# boardSchematic.net
KiCad netlist of a schematic drawn in EAGLE
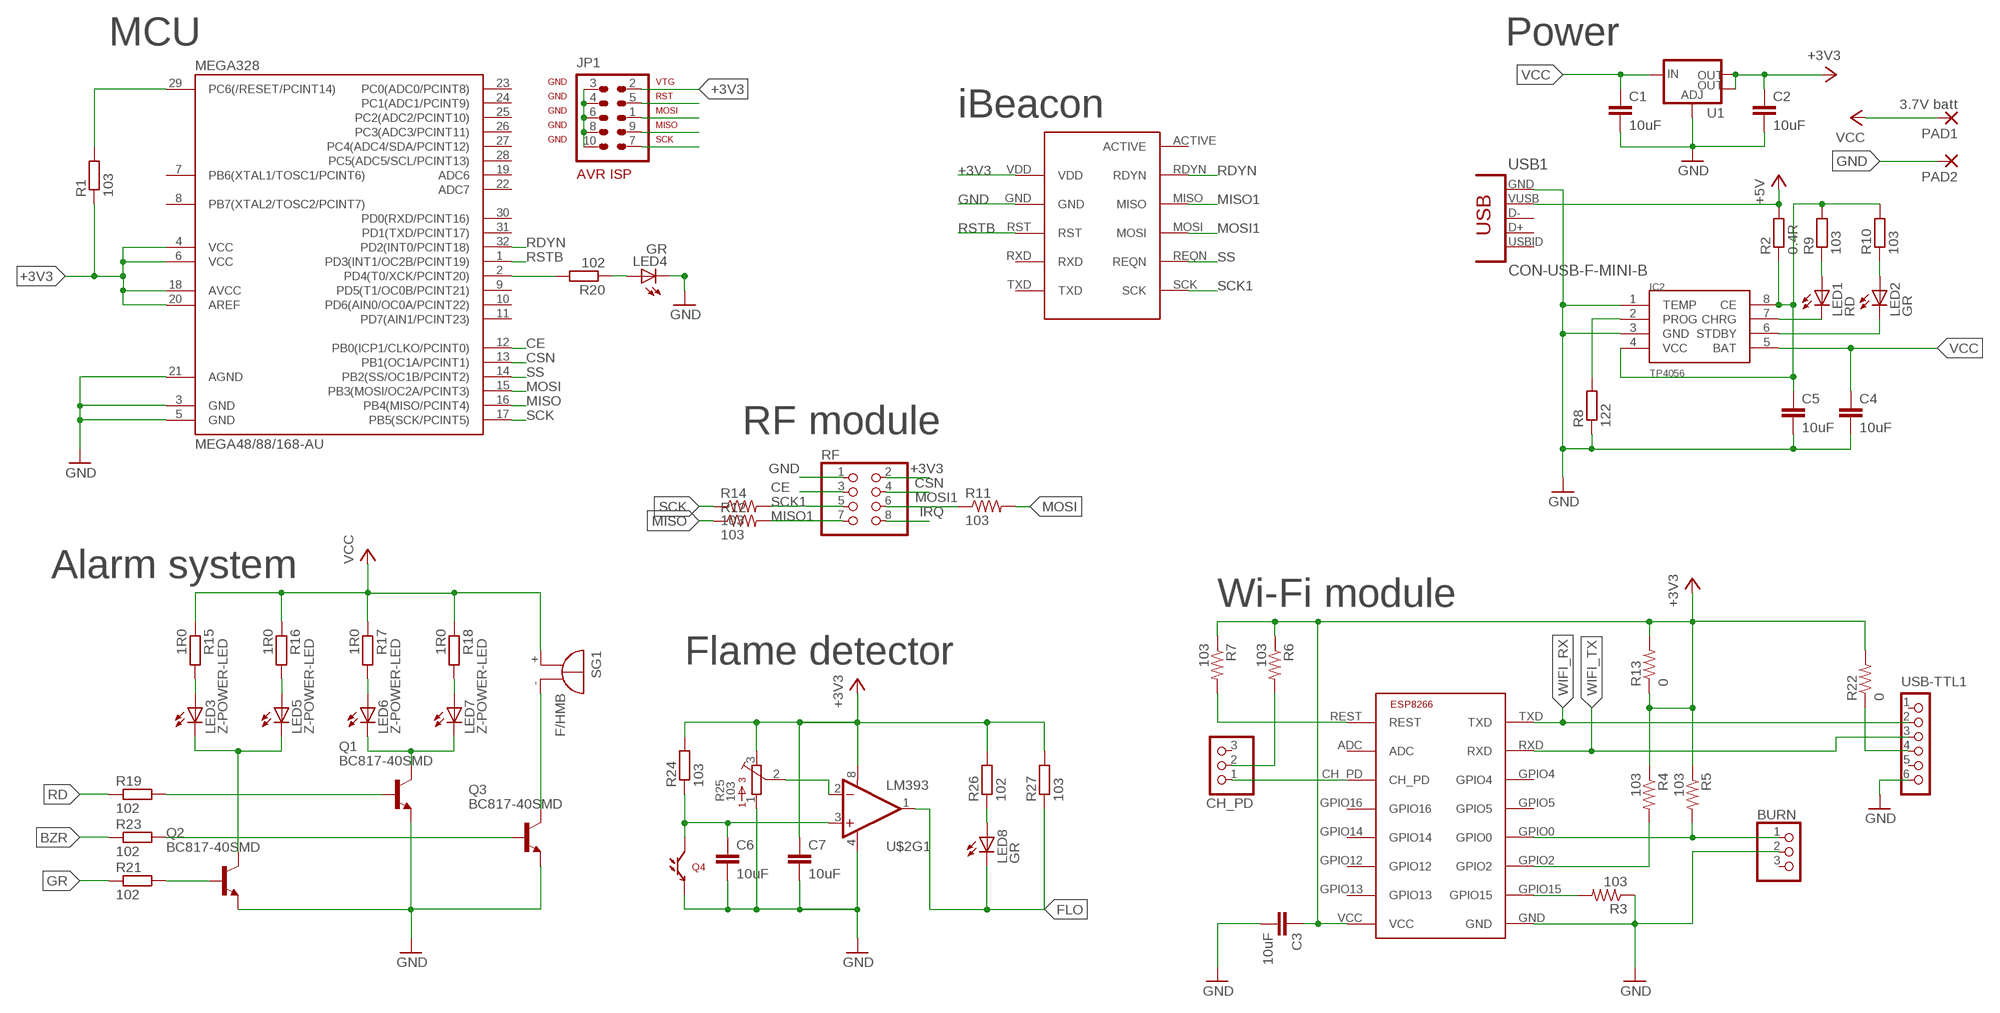
[diagram p0: schematic, sheet 1]

(export (version "E")
  (design (tool "Eeschema 10.0.6"))
  (components
    (comp (ref "BEACON")
      (value "MOD-NRF8001MOD-NRF8001")
      (footprint "eagle-import:MOD-NRF8001")
      (libsource (lib "eagle-import") (part "MOD-NRF8001MOD-NRF8001"))
    )
    (comp (ref "BURN")
      (value "PINHD-1X3")
      (footprint "eagle-import:1X03")
      (libsource (lib "eagle-import") (part "PINHD-1X3"))
    )
    (comp (ref "C1")
      (value "10uF")
      (footprint "eagle-import:C0805")
      (libsource (lib "eagle-import") (part "C-EUC0805"))
    )
    (comp (ref "C2")
      (value "10uF")
      (footprint "eagle-import:C0805")
      (libsource (lib "eagle-import") (part "C-EUC0805"))
    )
    (comp (ref "C3")
      (value "10uF")
      (footprint "eagle-import:C0805")
      (libsource (lib "eagle-import") (part "C-EUC0805"))
    )
    (comp (ref "C4")
      (value "10uF")
      (footprint "eagle-import:C1210")
      (libsource (lib "eagle-import") (part "C-EUC1210"))
    )
    (comp (ref "C5")
      (value "10uF")
      (footprint "eagle-import:C1210")
      (libsource (lib "eagle-import") (part "C-EUC1210"))
    )
    (comp (ref "C6")
      (value "10uF")
      (footprint "eagle-import:C0805")
      (libsource (lib "eagle-import") (part "C-EUC0805"))
    )
    (comp (ref "C7")
      (value "10uF")
      (footprint "eagle-import:C0805")
      (libsource (lib "eagle-import") (part "C-EUC0805"))
    )
    (comp (ref "CH_PD")
      (value "PINHD-1X3")
      (footprint "eagle-import:1X03")
      (libsource (lib "eagle-import") (part "PINHD-1X3"))
    )
    (comp (ref "IC2")
      (value "TP4056")
      (footprint "eagle-import:SOP-8")
      (libsource (lib "eagle-import") (part "TP4056"))
    )
    (comp (ref "JP1")
      (value "AVR-ISP-10")
      (footprint "eagle-import:AVR-ISP-10")
      (libsource (lib "eagle-import") (part "AVR-ISP-10"))
    )
    (comp (ref "LED1")
      (value "RD")
      (footprint "eagle-import:SML0805")
      (libsource (lib "eagle-import") (part "LEDSML0805"))
    )
    (comp (ref "LED2")
      (value "GR")
      (footprint "eagle-import:SML0805")
      (libsource (lib "eagle-import") (part "LEDSML0805"))
    )
    (comp (ref "LED3")
      (value "Z-POWER-LED")
      (footprint "eagle-import:Z-POWER-LED-PCB-TYPE")
      (libsource (lib "eagle-import") (part "Z-POWER-LED"))
    )
    (comp (ref "LED4")
      (value "GR")
      (footprint "eagle-import:SML0805")
      (libsource (lib "eagle-import") (part "LEDSML0805"))
    )
    (comp (ref "LED5")
      (value "Z-POWER-LED")
      (footprint "eagle-import:Z-POWER-LED-PCB-TYPE")
      (libsource (lib "eagle-import") (part "Z-POWER-LED"))
    )
    (comp (ref "LED6")
      (value "Z-POWER-LED")
      (footprint "eagle-import:Z-POWER-LED-PCB-TYPE")
      (libsource (lib "eagle-import") (part "Z-POWER-LED"))
    )
    (comp (ref "LED7")
      (value "Z-POWER-LED")
      (footprint "eagle-import:Z-POWER-LED-PCB-TYPE")
      (libsource (lib "eagle-import") (part "Z-POWER-LED"))
    )
    (comp (ref "LED8")
      (value "GR")
      (footprint "eagle-import:SML0805")
      (libsource (lib "eagle-import") (part "LEDSML0805"))
    )
    (comp (ref "MEGA328")
      (value "MEGA48/88/168-AU")
      (footprint "eagle-import:TQFP32-08")
      (libsource (lib "eagle-import") (part "MEGA48/88/168-AU"))
    )
    (comp (ref "PAD1")
      (value "3.7V batt")
      (footprint "eagle-import:SMD2,54-5,08")
      (libsource (lib "eagle-import") (part "SMD5"))
    )
    (comp (ref "PAD2")
      (value "SMD5")
      (footprint "eagle-import:SMD2,54-5,08")
      (libsource (lib "eagle-import") (part "SMD5"))
    )
    (comp (ref "Q1")
      (value "BC817-40SMD")
      (footprint "eagle-import:SOT23-BEC")
      (libsource (lib "eagle-import") (part "BC817SMD-40"))
    )
    (comp (ref "Q2")
      (value "BC817-40SMD")
      (footprint "eagle-import:SOT23-BEC")
      (libsource (lib "eagle-import") (part "BC817SMD-40"))
    )
    (comp (ref "Q3")
      (value "BC817-40SMD")
      (footprint "eagle-import:SOT23-BEC")
      (libsource (lib "eagle-import") (part "BC817SMD-40"))
    )
    (comp (ref "Q4")
      (value "LTR-301")
      (footprint "eagle-import:LTR-301")
      (libsource (lib "eagle-import") (part "LTR-301"))
    )
    (comp (ref "R1")
      (value "103")
      (footprint "eagle-import:R0805")
      (libsource (lib "eagle-import") (part "R-EU_R0805"))
    )
    (comp (ref "R2")
      (value "0.4R")
      (footprint "eagle-import:R1210W")
      (libsource (lib "eagle-import") (part "R-EU_R1210W"))
    )
    (comp (ref "R3")
      (value "103")
      (footprint "eagle-import:R0805")
      (libsource (lib "eagle-import") (part "R-US_R0805"))
    )
    (comp (ref "R4")
      (value "103")
      (footprint "eagle-import:R0805")
      (libsource (lib "eagle-import") (part "R-US_R0805"))
    )
    (comp (ref "R5")
      (value "103")
      (footprint "eagle-import:R0805")
      (libsource (lib "eagle-import") (part "R-US_R0805"))
    )
    (comp (ref "R6")
      (value "103")
      (footprint "eagle-import:R0805")
      (libsource (lib "eagle-import") (part "R-US_R0805"))
    )
    (comp (ref "R7")
      (value "103")
      (footprint "eagle-import:R0805")
      (libsource (lib "eagle-import") (part "R-US_R0805"))
    )
    (comp (ref "R8")
      (value "122")
      (footprint "eagle-import:R0805")
      (libsource (lib "eagle-import") (part "R-EU_R0805"))
    )
    (comp (ref "R9")
      (value "103")
      (footprint "eagle-import:R0805")
      (libsource (lib "eagle-import") (part "R-EU_R0805"))
    )
    (comp (ref "R10")
      (value "103")
      (footprint "eagle-import:R0805")
      (libsource (lib "eagle-import") (part "R-EU_R0805"))
    )
    (comp (ref "R11")
      (value "103")
      (footprint "eagle-import:R0805")
      (libsource (lib "eagle-import") (part "R-US_R0805"))
    )
    (comp (ref "R12")
      (value "103")
      (footprint "eagle-import:R0805")
      (libsource (lib "eagle-import") (part "R-US_R0805"))
    )
    (comp (ref "R13")
      (value "0")
      (footprint "eagle-import:R1206")
      (libsource (lib "eagle-import") (part "R-US_R1206"))
    )
    (comp (ref "R14")
      (value "103")
      (footprint "eagle-import:R0805")
      (libsource (lib "eagle-import") (part "R-US_R0805"))
    )
    (comp (ref "R15")
      (value "1R0")
      (footprint "eagle-import:R1206")
      (libsource (lib "eagle-import") (part "R-EU_R1206"))
    )
    (comp (ref "R16")
      (value "1R0")
      (footprint "eagle-import:R1206")
      (libsource (lib "eagle-import") (part "R-EU_R1206"))
    )
    (comp (ref "R17")
      (value "1R0")
      (footprint "eagle-import:R1206")
      (libsource (lib "eagle-import") (part "R-EU_R1206"))
    )
    (comp (ref "R18")
      (value "1R0")
      (footprint "eagle-import:R1206")
      (libsource (lib "eagle-import") (part "R-EU_R1206"))
    )
    (comp (ref "R19")
      (value "102")
      (footprint "eagle-import:R0805")
      (libsource (lib "eagle-import") (part "R-EU_R0805"))
    )
    (comp (ref "R20")
      (value "102")
      (footprint "eagle-import:R0805")
      (libsource (lib "eagle-import") (part "R-EU_R0805"))
    )
    (comp (ref "R21")
      (value "102")
      (footprint "eagle-import:R0805")
      (libsource (lib "eagle-import") (part "R-EU_R0805"))
    )
    (comp (ref "R22")
      (value "0")
      (footprint "eagle-import:R1206")
      (libsource (lib "eagle-import") (part "R-US_R1206"))
    )
    (comp (ref "R23")
      (value "102")
      (footprint "eagle-import:R0805")
      (libsource (lib "eagle-import") (part "R-EU_R0805"))
    )
    (comp (ref "R24")
      (value "103")
      (footprint "eagle-import:R0805")
      (libsource (lib "eagle-import") (part "R-EU_R0805"))
    )
    (comp (ref "R25")
      (value "103")
      (footprint "eagle-import:3362P")
      (libsource (lib "eagle-import") (part "3362P"))
    )
    (comp (ref "R26")
      (value "102")
      (footprint "eagle-import:R0805")
      (libsource (lib "eagle-import") (part "R-EU_R0805"))
    )
    (comp (ref "R27")
      (value "103")
      (footprint "eagle-import:R0805")
      (libsource (lib "eagle-import") (part "R-EU_R0805"))
    )
    (comp (ref "RF")
      (value "PINHD-2X4")
      (footprint "eagle-import:2X04")
      (libsource (lib "eagle-import") (part "PINHD-2X4"))
    )
    (comp (ref "SG1")
      (value "F/HMB")
      (footprint "eagle-import:F_HMB")
      (libsource (lib "eagle-import") (part "F/HMB"))
    )
    (comp (ref "U$1")
      (value "ESP8266")
      (footprint "eagle-import:ESP-03")
      (libsource (lib "eagle-import") (part "ESP8266"))
    )
    (comp (ref "U$2")
      (value "LM393")
      (footprint "eagle-import:SO08")
      (libsource (lib "eagle-import") (part "LM393"))
    )
    (comp (ref "U1")
      (value "V_REG_LM1117SOT223")
      (footprint "eagle-import:SOT223")
      (libsource (lib "eagle-import") (part "V_REG_LM1117SOT223"))
    )
    (comp (ref "USB-TTL1")
      (value "CON_HEADER_1X06-SMD-RIGHT-ANGLED")
      (footprint "eagle-import:M1X6_MALE_RIGHT_ANGLED_SMD")
      (libsource (lib "eagle-import") (part "CON_HEADER_1X06-SMD-RIGHT-ANGLED"))
    )
    (comp (ref "USB1")
      (value "CON-USB-F-MINI-B")
      (footprint "eagle-import:CONN_USB_MINI-B")
      (libsource (lib "eagle-import") (part "CON-USB-F-MINI-B"))
    )
  )
  (nets
    (net (code "1") (name "+3V3") (class "Default")
      (node (ref "BEACON") (pin "VDD") (pinfunction "VDD_VDD") (pintype "power_in"))
      (node (ref "C2") (pin "1") (pinfunction "1_1") (pintype "passive"))
      (node (ref "C3") (pin "1") (pinfunction "1_1") (pintype "passive"))
      (node (ref "C7") (pin "1") (pinfunction "1_1") (pintype "passive"))
      (node (ref "JP1") (pin "2") (pinfunction "2_2") (pintype "passive"))
      (node (ref "MEGA328") (pin "18") (pinfunction "AVCC_18") (pintype "passive"))
      (node (ref "MEGA328") (pin "20") (pinfunction "AREF_20") (pintype "passive"))
      (node (ref "MEGA328") (pin "4") (pinfunction "VCC_4") (pintype "power_in"))
      (node (ref "MEGA328") (pin "6") (pinfunction "VCC_6") (pintype "power_in"))
      (node (ref "R1") (pin "1") (pinfunction "1_1") (pintype "passive"))
      (node (ref "R13") (pin "1") (pinfunction "1_1") (pintype "passive"))
      (node (ref "R13") (pin "2") (pinfunction "2_2") (pintype "passive"))
      (node (ref "R22") (pin "2") (pinfunction "2_2") (pintype "passive"))
      (node (ref "R24") (pin "2") (pinfunction "2_2") (pintype "passive"))
      (node (ref "R25") (pin "3") (pinfunction "3_3") (pintype "passive"))
      (node (ref "R26") (pin "2") (pinfunction "2_2") (pintype "passive"))
      (node (ref "R27") (pin "2") (pinfunction "2_2") (pintype "passive"))
      (node (ref "R4") (pin "1") (pinfunction "1_1") (pintype "passive"))
      (node (ref "R5") (pin "1") (pinfunction "1_1") (pintype "passive"))
      (node (ref "R6") (pin "1") (pinfunction "1_1") (pintype "passive"))
      (node (ref "R7") (pin "1") (pinfunction "1_1") (pintype "passive"))
      (node (ref "RF") (pin "2") (pinfunction "2_2") (pintype "passive"))
      (node (ref "U$1") (pin "VCC") (pinfunction "VCC_VCC") (pintype "bidirectional"))
      (node (ref "U$2") (pin "8") (pinfunction "V+_8") (pintype "power_in"))
      (node (ref "U1") (pin "2") (pinfunction "OUT_2") (pintype "output"))
      (node (ref "U1") (pin "4") (pinfunction "OUT_4") (pintype "output"))
    )
    (net (code "2") (name "+5V") (class "Default")
      (node (ref "R2") (pin "2") (pinfunction "2_2") (pintype "passive"))
      (node (ref "USB1") (pin "VUSB") (pinfunction "VUSB_VUSB") (pintype "bidirectional"))
    )
    (net (code "3") (name "/CE") (class "Default")
      (node (ref "MEGA328") (pin "12") (pinfunction "PB0(ICP1/CLKO/PCINT0)_12") (pintype "bidirectional"))
      (node (ref "RF") (pin "3") (pinfunction "3_3") (pintype "passive"))
    )
    (net (code "4") (name "/CSN") (class "Default")
      (node (ref "MEGA328") (pin "13") (pinfunction "PB1(OC1A/PCINT1)_13") (pintype "bidirectional"))
      (node (ref "RF") (pin "4") (pinfunction "4_4") (pintype "passive"))
    )
    (net (code "5") (name "/IRQ") (class "Default")
      (node (ref "RF") (pin "8") (pinfunction "8_8") (pintype "passive"))
    )
    (net (code "6") (name "/MISO1") (class "Default")
      (node (ref "BEACON") (pin "MISO") (pinfunction "MISO_MISO") (pintype "output"))
      (node (ref "R12") (pin "2") (pinfunction "2_2") (pintype "passive"))
      (node (ref "RF") (pin "7") (pinfunction "7_7") (pintype "passive"))
    )
    (net (code "7") (name "/MOSI1") (class "Default")
      (node (ref "BEACON") (pin "MOSI") (pinfunction "MOSI_MOSI") (pintype "input"))
      (node (ref "R11") (pin "1") (pinfunction "1_1") (pintype "passive"))
      (node (ref "RF") (pin "6") (pinfunction "6_6") (pintype "passive"))
    )
    (net (code "8") (name "/RDYN") (class "Default")
      (node (ref "BEACON") (pin "RDYN") (pinfunction "RDYN_RDYN") (pintype "output"))
      (node (ref "MEGA328") (pin "32") (pinfunction "PD2(INT0/PCINT18)_32") (pintype "bidirectional"))
    )
    (net (code "9") (name "/RST") (class "Default")
      (node (ref "JP1") (pin "5") (pinfunction "5_5") (pintype "passive"))
      (node (ref "MEGA328") (pin "29") (pinfunction "PC6(/RESET/PCINT14)_29") (pintype "bidirectional"))
      (node (ref "R1") (pin "2") (pinfunction "2_2") (pintype "passive"))
    )
    (net (code "10") (name "/RSTB") (class "Default")
      (node (ref "BEACON") (pin "RST") (pinfunction "RST_RST") (pintype "input"))
      (node (ref "MEGA328") (pin "1") (pinfunction "PD3(INT1/OC2B/PCINT19)_1") (pintype "bidirectional"))
    )
    (net (code "11") (name "/SCK1") (class "Default")
      (node (ref "BEACON") (pin "SCK") (pinfunction "SCK_SCK") (pintype "input"))
      (node (ref "R14") (pin "2") (pinfunction "2_2") (pintype "passive"))
      (node (ref "RF") (pin "5") (pinfunction "5_5") (pintype "passive"))
    )
    (net (code "12") (name "/SS") (class "Default")
      (node (ref "BEACON") (pin "REQN") (pinfunction "REQN_REQN") (pintype "input"))
      (node (ref "MEGA328") (pin "14") (pinfunction "PB2(SS/OC1B/PCINT2)_14") (pintype "bidirectional"))
    )
    (net (code "13") (name "BZR") (class "Default")
      (node (ref "R23") (pin "1") (pinfunction "1_1") (pintype "passive"))
    )
    (net (code "14") (name "FLO") (class "Default")
      (node (ref "LED8") (pin "C") (pinfunction "C_C") (pintype "passive"))
      (node (ref "R27") (pin "1") (pinfunction "1_1") (pintype "passive"))
      (node (ref "U$2") (pin "1") (pinfunction "OUT_1") (pintype "output"))
    )
    (net (code "15") (name "GND") (class "Default")
      (node (ref "BEACON") (pin "GND") (pinfunction "GND_GND") (pintype "power_in"))
      (node (ref "BURN") (pin "2") (pinfunction "2_2") (pintype "passive"))
      (node (ref "C1") (pin "2") (pinfunction "2_2") (pintype "passive"))
      (node (ref "C2") (pin "2") (pinfunction "2_2") (pintype "passive"))
      (node (ref "C3") (pin "2") (pinfunction "2_2") (pintype "passive"))
      (node (ref "C4") (pin "2") (pinfunction "2_2") (pintype "passive"))
      (node (ref "C5") (pin "2") (pinfunction "2_2") (pintype "passive"))
      (node (ref "C6") (pin "2") (pinfunction "2_2") (pintype "passive"))
      (node (ref "C7") (pin "2") (pinfunction "2_2") (pintype "passive"))
      (node (ref "IC2") (pin "1") (pinfunction "TEMP_1") (pintype "bidirectional"))
      (node (ref "IC2") (pin "3") (pinfunction "GND_3") (pintype "bidirectional"))
      (node (ref "JP1") (pin "10") (pinfunction "10_10") (pintype "passive"))
      (node (ref "JP1") (pin "3") (pinfunction "3_3") (pintype "passive"))
      (node (ref "JP1") (pin "4") (pinfunction "4_4") (pintype "passive"))
      (node (ref "JP1") (pin "6") (pinfunction "6_6") (pintype "passive"))
      (node (ref "JP1") (pin "8") (pinfunction "8_8") (pintype "passive"))
      (node (ref "LED4") (pin "C") (pinfunction "C_C") (pintype "passive"))
      (node (ref "MEGA328") (pin "21") (pinfunction "AGND_21") (pintype "power_in"))
      (node (ref "MEGA328") (pin "3") (pinfunction "GND_3") (pintype "power_in"))
      (node (ref "MEGA328") (pin "5") (pinfunction "GND_5") (pintype "power_in"))
      (node (ref "PAD2") (pin "1") (pinfunction "P_1") (pintype "passive"))
      (node (ref "Q1") (pin "E") (pinfunction "E_E") (pintype "passive"))
      (node (ref "Q2") (pin "E") (pinfunction "E_E") (pintype "passive"))
      (node (ref "Q3") (pin "E") (pinfunction "E_E") (pintype "passive"))
      (node (ref "Q4") (pin "E") (pinfunction "E_E") (pintype "bidirectional"))
      (node (ref "R25") (pin "1") (pinfunction "1_1") (pintype "passive"))
      (node (ref "R3") (pin "1") (pinfunction "1_1") (pintype "passive"))
      (node (ref "R8") (pin "1") (pinfunction "1_1") (pintype "passive"))
      (node (ref "RF") (pin "1") (pinfunction "1_1") (pintype "passive"))
      (node (ref "U$1") (pin "GND") (pinfunction "GND_GND") (pintype "bidirectional"))
      (node (ref "U$2") (pin "4") (pinfunction "V-_4") (pintype "power_in"))
      (node (ref "U1") (pin "1") (pinfunction "ADJ_1") (pintype "input"))
      (node (ref "USB-TTL1") (pin "6") (pinfunction "6_6") (pintype "passive"))
      (node (ref "USB1") (pin "GND") (pinfunction "GND_GND") (pintype "bidirectional"))
    )
    (net (code "16") (name "GR") (class "Default")
      (node (ref "R21") (pin "1") (pinfunction "1_1") (pintype "passive"))
    )
    (net (code "17") (name "MISO") (class "Default")
      (node (ref "JP1") (pin "9") (pinfunction "9_9") (pintype "passive"))
      (node (ref "MEGA328") (pin "16") (pinfunction "PB4(MISO/PCINT4)_16") (pintype "bidirectional"))
      (node (ref "R12") (pin "1") (pinfunction "1_1") (pintype "passive"))
    )
    (net (code "18") (name "MOSI") (class "Default")
      (node (ref "JP1") (pin "1") (pinfunction "1_1") (pintype "passive"))
      (node (ref "MEGA328") (pin "15") (pinfunction "PB3(MOSI/OC2A/PCINT3)_15") (pintype "bidirectional"))
      (node (ref "R11") (pin "2") (pinfunction "2_2") (pintype "passive"))
    )
    (net (code "19") (name "Net-(BURN-Pad1)") (class "Default")
      (node (ref "BURN") (pin "1") (pinfunction "1_1") (pintype "passive"))
      (node (ref "R5") (pin "2") (pinfunction "2_2") (pintype "passive"))
      (node (ref "U$1") (pin "GPIO0") (pinfunction "GPIO0_GPIO0") (pintype "bidirectional"))
    )
    (net (code "20") (name "Net-(CH_PD-Pad1)") (class "Default")
      (node (ref "CH_PD") (pin "1") (pinfunction "1_1") (pintype "passive"))
      (node (ref "U$1") (pin "CH_PD") (pinfunction "CH_PD_CH_PD") (pintype "bidirectional"))
    )
    (net (code "21") (name "Net-(CH_PD-Pad2)") (class "Default")
      (node (ref "CH_PD") (pin "2") (pinfunction "2_2") (pintype "passive"))
      (node (ref "R6") (pin "2") (pinfunction "2_2") (pintype "passive"))
    )
    (net (code "22") (name "Net-(IC2-CE)") (class "Default")
      (node (ref "C5") (pin "1") (pinfunction "1_1") (pintype "passive"))
      (node (ref "IC2") (pin "4") (pinfunction "VCC_4") (pintype "bidirectional"))
      (node (ref "IC2") (pin "8") (pinfunction "CE_8") (pintype "bidirectional"))
      (node (ref "R10") (pin "2") (pinfunction "2_2") (pintype "passive"))
      (node (ref "R2") (pin "1") (pinfunction "1_1") (pintype "passive"))
      (node (ref "R9") (pin "2") (pinfunction "2_2") (pintype "passive"))
    )
    (net (code "23") (name "Net-(IC2-CHRG)") (class "Default")
      (node (ref "IC2") (pin "7") (pinfunction "CHRG_7") (pintype "bidirectional"))
      (node (ref "LED1") (pin "C") (pinfunction "C_C") (pintype "passive"))
    )
    (net (code "24") (name "Net-(IC2-PROG)") (class "Default")
      (node (ref "IC2") (pin "2") (pinfunction "PROG_2") (pintype "bidirectional"))
      (node (ref "R8") (pin "2") (pinfunction "2_2") (pintype "passive"))
    )
    (net (code "25") (name "Net-(IC2-STDBY)") (class "Default")
      (node (ref "IC2") (pin "6") (pinfunction "STDBY_6") (pintype "bidirectional"))
      (node (ref "LED2") (pin "C") (pinfunction "C_C") (pintype "passive"))
    )
    (net (code "26") (name "Net-(LED1-PadA)") (class "Default")
      (node (ref "LED1") (pin "A") (pinfunction "A_A") (pintype "passive"))
      (node (ref "R9") (pin "1") (pinfunction "1_1") (pintype "passive"))
    )
    (net (code "27") (name "Net-(LED2-PadA)") (class "Default")
      (node (ref "LED2") (pin "A") (pinfunction "A_A") (pintype "passive"))
      (node (ref "R10") (pin "1") (pinfunction "1_1") (pintype "passive"))
    )
    (net (code "28") (name "Net-(LED3-PadA)") (class "Default")
      (node (ref "LED3") (pin "A") (pinfunction "A_A") (pintype "passive"))
      (node (ref "R15") (pin "2") (pinfunction "2_2") (pintype "passive"))
    )
    (net (code "29") (name "Net-(LED3-PadC)") (class "Default")
      (node (ref "LED3") (pin "C") (pinfunction "C_C") (pintype "passive"))
      (node (ref "LED5") (pin "C") (pinfunction "C_C") (pintype "passive"))
      (node (ref "Q2") (pin "C") (pinfunction "C_C") (pintype "passive"))
    )
    (net (code "30") (name "Net-(LED4-PadA)") (class "Default")
      (node (ref "LED4") (pin "A") (pinfunction "A_A") (pintype "passive"))
      (node (ref "R20") (pin "1") (pinfunction "1_1") (pintype "passive"))
    )
    (net (code "31") (name "Net-(LED5-PadA)") (class "Default")
      (node (ref "LED5") (pin "A") (pinfunction "A_A") (pintype "passive"))
      (node (ref "R16") (pin "2") (pinfunction "2_2") (pintype "passive"))
    )
    (net (code "32") (name "Net-(LED6-PadA)") (class "Default")
      (node (ref "LED6") (pin "A") (pinfunction "A_A") (pintype "passive"))
      (node (ref "R17") (pin "2") (pinfunction "2_2") (pintype "passive"))
    )
    (net (code "33") (name "Net-(LED6-PadC)") (class "Default")
      (node (ref "LED6") (pin "C") (pinfunction "C_C") (pintype "passive"))
      (node (ref "LED7") (pin "C") (pinfunction "C_C") (pintype "passive"))
      (node (ref "Q1") (pin "C") (pinfunction "C_C") (pintype "passive"))
    )
    (net (code "34") (name "Net-(LED7-PadA)") (class "Default")
      (node (ref "LED7") (pin "A") (pinfunction "A_A") (pintype "passive"))
      (node (ref "R18") (pin "2") (pinfunction "2_2") (pintype "passive"))
    )
    (net (code "35") (name "Net-(LED8-PadA)") (class "Default")
      (node (ref "LED8") (pin "A") (pinfunction "A_A") (pintype "passive"))
      (node (ref "R26") (pin "1") (pinfunction "1_1") (pintype "passive"))
    )
    (net (code "36") (name "Net-(MEGA328-PD4(T0{slash}XCK{slash}PCINT20))") (class "Default")
      (node (ref "MEGA328") (pin "2") (pinfunction "PD4(T0/XCK/PCINT20)_2") (pintype "bidirectional"))
      (node (ref "R20") (pin "2") (pinfunction "2_2") (pintype "passive"))
    )
    (net (code "37") (name "Net-(Q1-PadB)") (class "Default")
      (node (ref "Q1") (pin "B") (pinfunction "B_B") (pintype "passive"))
      (node (ref "R19") (pin "2") (pinfunction "2_2") (pintype "passive"))
    )
    (net (code "38") (name "Net-(Q2-PadB)") (class "Default")
      (node (ref "Q2") (pin "B") (pinfunction "B_B") (pintype "passive"))
      (node (ref "R21") (pin "2") (pinfunction "2_2") (pintype "passive"))
    )
    (net (code "39") (name "Net-(Q3-PadB)") (class "Default")
      (node (ref "Q3") (pin "B") (pinfunction "B_B") (pintype "passive"))
      (node (ref "R23") (pin "2") (pinfunction "2_2") (pintype "passive"))
    )
    (net (code "40") (name "Net-(Q3-PadC)") (class "Default")
      (node (ref "Q3") (pin "C") (pinfunction "C_C") (pintype "passive"))
      (node (ref "SG1") (pin "-") (pinfunction "-_-") (pintype "passive"))
    )
    (net (code "41") (name "Net-(R3-Pad2)") (class "Default")
      (node (ref "R3") (pin "2") (pinfunction "2_2") (pintype "passive"))
      (node (ref "U$1") (pin "GPIO15") (pinfunction "GPIO15_GPIO15") (pintype "bidirectional"))
    )
    (net (code "42") (name "Net-(R4-Pad2)") (class "Default")
      (node (ref "R4") (pin "2") (pinfunction "2_2") (pintype "passive"))
      (node (ref "U$1") (pin "GPIO2") (pinfunction "GPIO2_GPIO2") (pintype "bidirectional"))
    )
    (net (code "43") (name "Net-(R7-Pad2)") (class "Default")
      (node (ref "R7") (pin "2") (pinfunction "2_2") (pintype "passive"))
      (node (ref "U$1") (pin "REST") (pinfunction "REST_REST") (pintype "bidirectional"))
    )
    (net (code "44") (name "Net-(R22-Pad1)") (class "Default")
      (node (ref "R22") (pin "1") (pinfunction "1_1") (pintype "passive"))
      (node (ref "USB-TTL1") (pin "4") (pinfunction "4_4") (pintype "passive"))
    )
    (net (code "45") (name "Net-(U$2A-+IN)") (class "Default")
      (node (ref "C6") (pin "1") (pinfunction "1_1") (pintype "passive"))
      (node (ref "Q4") (pin "C") (pinfunction "C_C") (pintype "bidirectional"))
      (node (ref "R24") (pin "1") (pinfunction "1_1") (pintype "passive"))
      (node (ref "U$2") (pin "3") (pinfunction "+IN_3") (pintype "input"))
    )
    (net (code "46") (name "Net-(U$2A--IN)") (class "Default")
      (node (ref "R25") (pin "2") (pinfunction "2_2") (pintype "passive"))
      (node (ref "U$2") (pin "2") (pinfunction "-IN_2") (pintype "input"))
    )
    (net (code "47") (name "RD") (class "Default")
      (node (ref "R19") (pin "1") (pinfunction "1_1") (pintype "passive"))
    )
    (net (code "48") (name "SCK") (class "Default")
      (node (ref "JP1") (pin "7") (pinfunction "7_7") (pintype "passive"))
      (node (ref "MEGA328") (pin "17") (pinfunction "PB5(SCK/PCINT5)_17") (pintype "bidirectional"))
      (node (ref "R14") (pin "1") (pinfunction "1_1") (pintype "passive"))
    )
    (net (code "49") (name "VCC") (class "Default")
      (node (ref "C1") (pin "1") (pinfunction "1_1") (pintype "passive"))
      (node (ref "C4") (pin "1") (pinfunction "1_1") (pintype "passive"))
      (node (ref "IC2") (pin "5") (pinfunction "BAT_5") (pintype "bidirectional"))
      (node (ref "PAD1") (pin "1") (pinfunction "P_1") (pintype "passive"))
      (node (ref "R15") (pin "1") (pinfunction "1_1") (pintype "passive"))
      (node (ref "R16") (pin "1") (pinfunction "1_1") (pintype "passive"))
      (node (ref "R17") (pin "1") (pinfunction "1_1") (pintype "passive"))
      (node (ref "R18") (pin "1") (pinfunction "1_1") (pintype "passive"))
      (node (ref "SG1") (pin "+") (pinfunction "+_+") (pintype "passive"))
      (node (ref "U1") (pin "3") (pinfunction "IN_3") (pintype "input"))
    )
    (net (code "50") (name "WIFI_RX") (class "Default")
      (node (ref "U$1") (pin "TXD") (pinfunction "TXD_TXD") (pintype "bidirectional"))
      (node (ref "USB-TTL1") (pin "2") (pinfunction "2_2") (pintype "bidirectional"))
    )
    (net (code "51") (name "WIFI_TX") (class "Default")
      (node (ref "U$1") (pin "RXD") (pinfunction "RXD_RXD") (pintype "bidirectional"))
      (node (ref "USB-TTL1") (pin "3") (pinfunction "3_3") (pintype "passive"))
    )
    (net (code "52") (name "unconnected-(BEACON-PadACTIVE)") (class "Default")
      (node (ref "BEACON") (pin "ACTIVE") (pinfunction "ACTIVE_ACTIVE") (pintype "output"))
    )
    (net (code "53") (name "unconnected-(BEACON-PadRXD)") (class "Default")
      (node (ref "BEACON") (pin "RXD") (pinfunction "RXD_RXD") (pintype "input"))
    )
    (net (code "54") (name "unconnected-(BEACON-PadTXD)") (class "Default")
      (node (ref "BEACON") (pin "TXD") (pinfunction "TXD_TXD") (pintype "output"))
    )
    (net (code "55") (name "unconnected-(BURN-Pad3)") (class "Default")
      (node (ref "BURN") (pin "3") (pinfunction "3_3") (pintype "passive"))
    )
    (net (code "56") (name "unconnected-(CH_PD-Pad3)") (class "Default")
      (node (ref "CH_PD") (pin "3") (pinfunction "3_3") (pintype "passive"))
    )
    (net (code "57") (name "unconnected-(MEGA328-ADC6-Pad19)") (class "Default")
      (node (ref "MEGA328") (pin "19") (pinfunction "ADC6_19") (pintype "passive"))
    )
    (net (code "58") (name "unconnected-(MEGA328-ADC7-Pad22)") (class "Default")
      (node (ref "MEGA328") (pin "22") (pinfunction "ADC7_22") (pintype "passive"))
    )
    (net (code "59") (name "unconnected-(MEGA328-PB6(XTAL1{slash}TOSC1{slash}PCINT6)-Pad7)") (class "Default")
      (node (ref "MEGA328") (pin "7") (pinfunction "PB6(XTAL1/TOSC1/PCINT6)_7") (pintype "bidirectional"))
    )
    (net (code "60") (name "unconnected-(MEGA328-PB7(XTAL2{slash}TOSC2{slash}PCINT7)-Pad8)") (class "Default")
      (node (ref "MEGA328") (pin "8") (pinfunction "PB7(XTAL2/TOSC2/PCINT7)_8") (pintype "bidirectional"))
    )
    (net (code "61") (name "unconnected-(MEGA328-PC0(ADC0{slash}PCINT8)-Pad23)") (class "Default")
      (node (ref "MEGA328") (pin "23") (pinfunction "PC0(ADC0/PCINT8)_23") (pintype "bidirectional"))
    )
    (net (code "62") (name "unconnected-(MEGA328-PC1(ADC1{slash}PCINT9)-Pad24)") (class "Default")
      (node (ref "MEGA328") (pin "24") (pinfunction "PC1(ADC1/PCINT9)_24") (pintype "bidirectional"))
    )
    (net (code "63") (name "unconnected-(MEGA328-PC2(ADC2{slash}PCINT10)-Pad25)") (class "Default")
      (node (ref "MEGA328") (pin "25") (pinfunction "PC2(ADC2/PCINT10)_25") (pintype "bidirectional"))
    )
    (net (code "64") (name "unconnected-(MEGA328-PC3(ADC3{slash}PCINT11)-Pad26)") (class "Default")
      (node (ref "MEGA328") (pin "26") (pinfunction "PC3(ADC3/PCINT11)_26") (pintype "bidirectional"))
    )
    (net (code "65") (name "unconnected-(MEGA328-PC4(ADC4{slash}SDA{slash}PCINT12)-Pad27)") (class "Default")
      (node (ref "MEGA328") (pin "27") (pinfunction "PC4(ADC4/SDA/PCINT12)_27") (pintype "bidirectional"))
    )
    (net (code "66") (name "unconnected-(MEGA328-PC5(ADC5{slash}SCL{slash}PCINT13)-Pad28)") (class "Default")
      (node (ref "MEGA328") (pin "28") (pinfunction "PC5(ADC5/SCL/PCINT13)_28") (pintype "bidirectional"))
    )
    (net (code "67") (name "unconnected-(MEGA328-PD0(RXD{slash}PCINT16)-Pad30)") (class "Default")
      (node (ref "MEGA328") (pin "30") (pinfunction "PD0(RXD/PCINT16)_30") (pintype "bidirectional"))
    )
    (net (code "68") (name "unconnected-(MEGA328-PD1(TXD{slash}PCINT17)-Pad31)") (class "Default")
      (node (ref "MEGA328") (pin "31") (pinfunction "PD1(TXD/PCINT17)_31") (pintype "bidirectional"))
    )
    (net (code "69") (name "unconnected-(MEGA328-PD5(T1{slash}OC0B{slash}PCINT21)-Pad9)") (class "Default")
      (node (ref "MEGA328") (pin "9") (pinfunction "PD5(T1/OC0B/PCINT21)_9") (pintype "bidirectional"))
    )
    (net (code "70") (name "unconnected-(MEGA328-PD6(AIN0{slash}OC0A{slash}PCINT22)-Pad10)") (class "Default")
      (node (ref "MEGA328") (pin "10") (pinfunction "PD6(AIN0/OC0A/PCINT22)_10") (pintype "bidirectional"))
    )
    (net (code "71") (name "unconnected-(MEGA328-PD7(AIN1{slash}PCINT23)-Pad11)") (class "Default")
      (node (ref "MEGA328") (pin "11") (pinfunction "PD7(AIN1/PCINT23)_11") (pintype "bidirectional"))
    )
    (net (code "72") (name "unconnected-(U$1-PadADC)") (class "Default")
      (node (ref "U$1") (pin "ADC") (pinfunction "ADC_ADC") (pintype "bidirectional"))
    )
    (net (code "73") (name "unconnected-(U$1-PadGPIO4)") (class "Default")
      (node (ref "U$1") (pin "GPIO4") (pinfunction "GPIO4_GPIO4") (pintype "bidirectional"))
    )
    (net (code "74") (name "unconnected-(U$1-PadGPIO5)") (class "Default")
      (node (ref "U$1") (pin "GPIO5") (pinfunction "GPIO5_GPIO5") (pintype "bidirectional"))
    )
    (net (code "75") (name "unconnected-(U$1-PadGPIO12)") (class "Default")
      (node (ref "U$1") (pin "GPIO12") (pinfunction "GPIO12_GPIO12") (pintype "bidirectional"))
    )
    (net (code "76") (name "unconnected-(U$1-PadGPIO13)") (class "Default")
      (node (ref "U$1") (pin "GPIO13") (pinfunction "GPIO13_GPIO13") (pintype "bidirectional"))
    )
    (net (code "77") (name "unconnected-(U$1-PadGPIO14)") (class "Default")
      (node (ref "U$1") (pin "GPIO14") (pinfunction "GPIO14_GPIO14") (pintype "bidirectional"))
    )
    (net (code "78") (name "unconnected-(U$1-PadGPIO16)") (class "Default")
      (node (ref "U$1") (pin "GPIO16") (pinfunction "GPIO16_GPIO16") (pintype "bidirectional"))
    )
    (net (code "79") (name "unconnected-(USB-TTL1-Pad1)") (class "Default")
      (node (ref "USB-TTL1") (pin "1") (pinfunction "1_1") (pintype "bidirectional"))
    )
    (net (code "80") (name "unconnected-(USB-TTL1-Pad5)") (class "Default")
      (node (ref "USB-TTL1") (pin "5") (pinfunction "5_5") (pintype "passive"))
    )
    (net (code "81") (name "unconnected-(USB1-PadD+)") (class "Default")
      (node (ref "USB1") (pin "D+") (pinfunction "D+_D+") (pintype "bidirectional"))
    )
    (net (code "82") (name "unconnected-(USB1-PadD-)") (class "Default")
      (node (ref "USB1") (pin "D-") (pinfunction "D-_D-") (pintype "bidirectional"))
    )
    (net (code "83") (name "unconnected-(USB1B-USBID-PadID)") (class "Default")
      (node (ref "USB1") (pin "ID") (pinfunction "USBID_ID") (pintype "bidirectional"))
    )
  )
)
